# LCDTFT_CTRL_FT811.net
KiCad netlist of a schematic drawn in Altium Designer
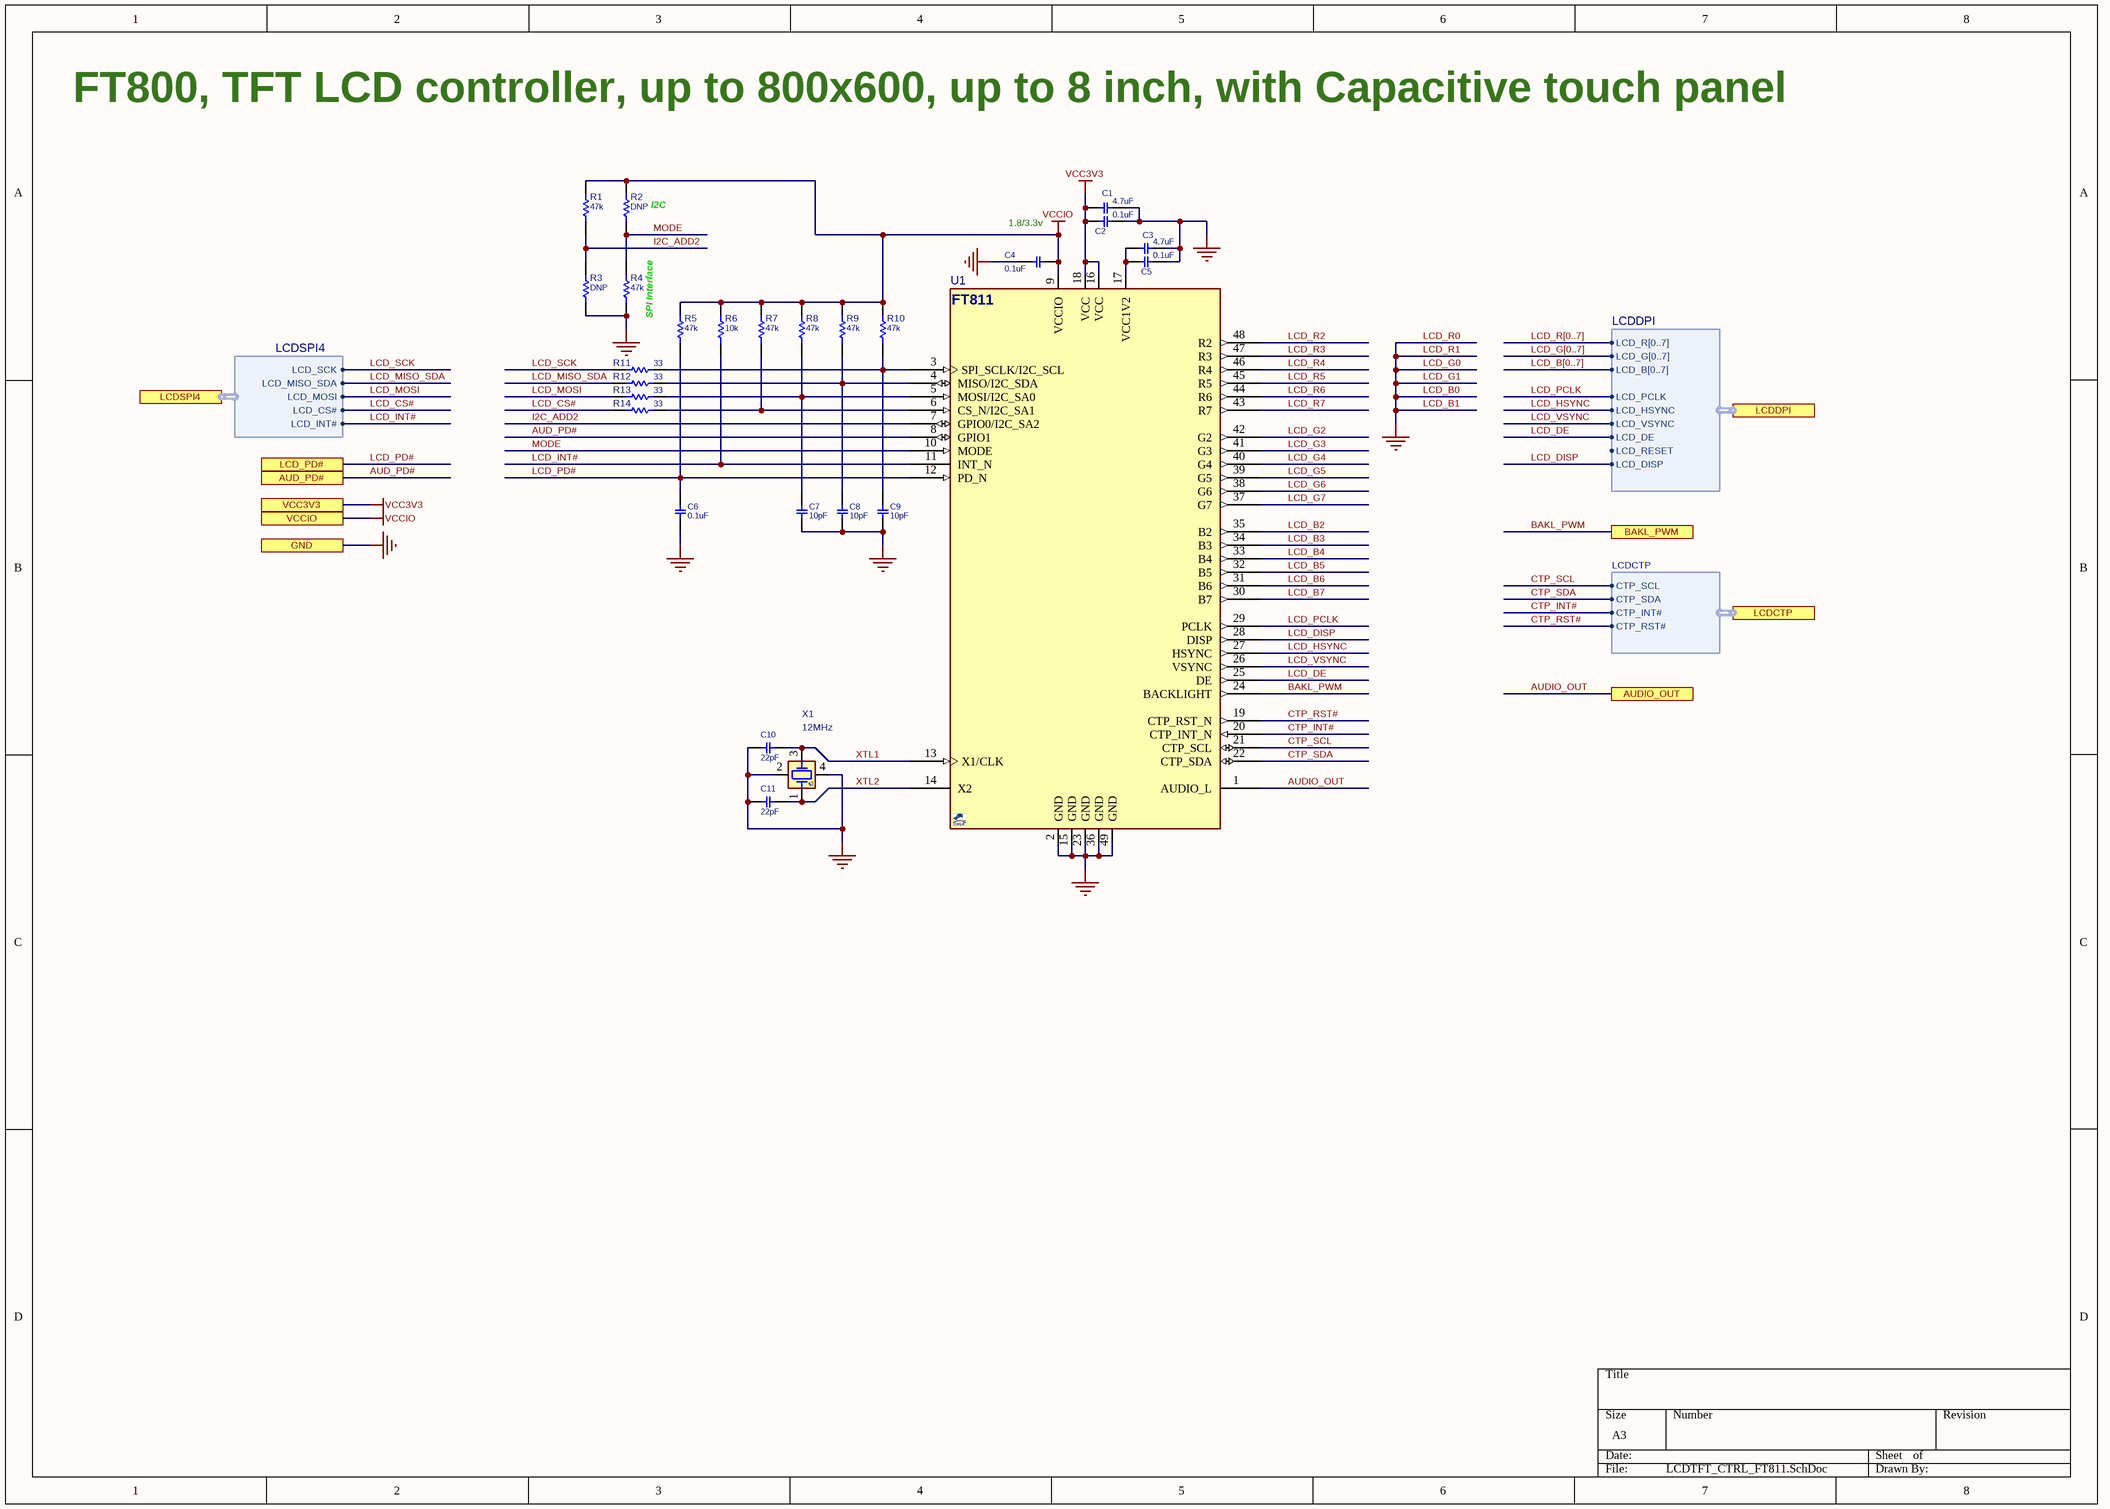
[diagram p0: LCDTFT_CTRL_FT811.SchDoc]

(export (version "E")
  (design (tool "Eeschema 10.0.6"))
  (components
    (comp (ref "C1")
      (value "4.7uF")
      (footprint "C0603")
      (description "CAP, MLCC")
      (libsource (lib "passive_smd") (part "CAP_SMD_MLCC"))
    )
    (comp (ref "C2")
      (value "0.1uF")
      (footprint "C0402")
      (description "CAP, MLCC")
      (fields (field (name "MANF_P#") "GRM155R71H104KE14D") (field (name "MANF") "Murata"))
      (libsource (lib "passive_smd") (part "CAP_SMD_MLCC"))
    )
    (comp (ref "C3")
      (value "4.7uF")
      (footprint "C0603")
      (description "CAP, MLCC")
      (libsource (lib "passive_smd") (part "CAP_SMD_MLCC"))
    )
    (comp (ref "C4")
      (value "0.1uF")
      (footprint "C0402")
      (description "CAP, MLCC")
      (fields (field (name "MANF_P#") "GRM155R71H104KE14D") (field (name "MANF") "Murata"))
      (libsource (lib "passive_smd") (part "CAP_SMD_MLCC"))
    )
    (comp (ref "C5")
      (value "0.1uF")
      (footprint "C0402")
      (description "CAP, MLCC")
      (fields (field (name "MANF_P#") "GRM155R71H104KE14D") (field (name "MANF") "Murata"))
      (libsource (lib "passive_smd") (part "CAP_SMD_MLCC"))
    )
    (comp (ref "C6")
      (value "0.1uF")
      (footprint "C0402")
      (description "CAP, MLCC")
      (fields (field (name "MANF_P#") "GRM155R71H104KE14D") (field (name "MANF") "Murata"))
      (libsource (lib "passive_smd") (part "CAP_SMD_MLCC"))
    )
    (comp (ref "C7")
      (value "10pF")
      (footprint "C0402")
      (description "CAP, MLCC")
      (libsource (lib "passive_smd") (part "CAP_SMD_MLCC"))
    )
    (comp (ref "C8")
      (value "10pF")
      (footprint "C0402")
      (description "CAP, MLCC")
      (libsource (lib "passive_smd") (part "CAP_SMD_MLCC"))
    )
    (comp (ref "C9")
      (value "10pF")
      (footprint "C0402")
      (description "CAP, MLCC")
      (libsource (lib "passive_smd") (part "CAP_SMD_MLCC"))
    )
    (comp (ref "C10")
      (value "22pF")
      (footprint "C0402")
      (description "CAP, MLCC")
      (libsource (lib "passive_smd") (part "CAP_SMD_MLCC"))
    )
    (comp (ref "C11")
      (value "22pF")
      (footprint "C0402")
      (description "CAP, MLCC")
      (libsource (lib "passive_smd") (part "CAP_SMD_MLCC"))
    )
    (comp (ref "R1")
      (value "47k")
      (footprint "R0402")
      (description "RESISTOR, SMD")
      (libsource (lib "passive_res_smd") (part "RES_SMD"))
    )
    (comp (ref "R2")
      (value "DNP")
      (footprint "R0402")
      (description "RESISTOR, SMD")
      (libsource (lib "passive_res_smd") (part "RES_SMD"))
    )
    (comp (ref "R3")
      (value "DNP")
      (footprint "R0402")
      (description "RESISTOR, SMD")
      (libsource (lib "passive_res_smd") (part "RES_SMD"))
    )
    (comp (ref "R4")
      (value "47k")
      (footprint "R0402")
      (description "RESISTOR, SMD")
      (libsource (lib "passive_res_smd") (part "RES_SMD"))
    )
    (comp (ref "R5")
      (value "47k")
      (footprint "R0402")
      (description "RESISTOR, SMD")
      (libsource (lib "passive_res_smd") (part "RES_SMD"))
    )
    (comp (ref "R6")
      (value "10k")
      (footprint "R0402")
      (description "RESISTOR, SMD")
      (libsource (lib "passive_res_smd") (part "RES_SMD"))
    )
    (comp (ref "R7")
      (value "47k")
      (footprint "R0402")
      (description "RESISTOR, SMD")
      (libsource (lib "passive_res_smd") (part "RES_SMD"))
    )
    (comp (ref "R8")
      (value "47k")
      (footprint "R0402")
      (description "RESISTOR, SMD")
      (libsource (lib "passive_res_smd") (part "RES_SMD"))
    )
    (comp (ref "R9")
      (value "47k")
      (footprint "R0402")
      (description "RESISTOR, SMD")
      (libsource (lib "passive_res_smd") (part "RES_SMD"))
    )
    (comp (ref "R10")
      (value "47k")
      (footprint "R0402")
      (description "RESISTOR, SMD")
      (libsource (lib "passive_res_smd") (part "RES_SMD"))
    )
    (comp (ref "R11")
      (value "33")
      (footprint "R0402")
      (description "RESISTOR, SMD")
      (libsource (lib "passive_res_smd") (part "RES_SMD"))
    )
    (comp (ref "R12")
      (value "33")
      (footprint "R0402")
      (description "RESISTOR, SMD")
      (libsource (lib "passive_res_smd") (part "RES_SMD"))
    )
    (comp (ref "R13")
      (value "33")
      (footprint "R0402")
      (description "RESISTOR, SMD")
      (libsource (lib "passive_res_smd") (part "RES_SMD"))
    )
    (comp (ref "R14")
      (value "33")
      (footprint "R0402")
      (description "RESISTOR, SMD")
      (libsource (lib "passive_res_smd") (part "RES_SMD"))
    )
    (comp (ref "U1")
      (value "FT811")
      (footprint "QFN50_48T")
      (description "LCD Display Controller, Embedded Video Engine, QFN-48")
      (fields (field (name "MANF") "FTDI/Bridgetek") (field (name "MANF_P#") "FT811Q"))
      (libsource (lib "lcdtft_controller") (part "FT811_QFN48"))
    )
    (comp (ref "X1")
      (value "12MHz")
      (footprint "XTL_4_3225")
      (description "Crystal 12MHz")
      (fields (field (name "MANF") "ECS") (field (name "MANF_P#") "ECS-120-18-33-JEM-TR"))
      (libsource (lib "crystal") (part "XTL_4_12MHz_3225"))
    )
  )
  (nets
    (net (code "4") (name "/AUDIO_OUT") (class "Default")
      (node (ref "U1") (pin "1") (pinfunction "AUDIO_L_1") (pintype "tri_state"))
    )
    (net (code "5") (name "/AUD_PD#") (class "Default")
      (node (ref "U1") (pin "8") (pinfunction "GPIO1_8") (pintype "bidirectional"))
    )
    (net (code "6") (name "/BAKL_PWM") (class "Default")
      (node (ref "U1") (pin "24") (pinfunction "BACKLIGHT_24") (pintype "output"))
    )
    (net (code "7") (name "/CTP_INT#") (class "Default")
      (node (ref "U1") (pin "20") (pinfunction "CTP_INT_N_20") (pintype "input"))
    )
    (net (code "8") (name "/CTP_RST#") (class "Default")
      (node (ref "U1") (pin "19") (pinfunction "CTP_RST_N_19") (pintype "output"))
    )
    (net (code "9") (name "/CTP_SCL") (class "Default")
      (node (ref "U1") (pin "21") (pinfunction "CTP_SCL_21") (pintype "bidirectional"))
    )
    (net (code "10") (name "/CTP_SDA") (class "Default")
      (node (ref "U1") (pin "22") (pinfunction "CTP_SDA_22") (pintype "bidirectional"))
    )
    (net (code "11") (name "/I2C_ADD2") (class "Default")
      (node (ref "R1") (pin "2") (pinfunction "2_2") (pintype "passive"))
      (node (ref "R3") (pin "1") (pinfunction "1_1") (pintype "passive"))
      (node (ref "U1") (pin "7") (pinfunction "GPIO0/I2C_SA2_7") (pintype "bidirectional"))
    )
    (net (code "12") (name "/LCD_B2") (class "Default")
      (node (ref "U1") (pin "35") (pinfunction "B2_35") (pintype "output"))
    )
    (net (code "13") (name "/LCD_B3") (class "Default")
      (node (ref "U1") (pin "34") (pinfunction "B3_34") (pintype "output"))
    )
    (net (code "14") (name "/LCD_B4") (class "Default")
      (node (ref "U1") (pin "33") (pinfunction "B4_33") (pintype "output"))
    )
    (net (code "15") (name "/LCD_B5") (class "Default")
      (node (ref "U1") (pin "32") (pinfunction "B5_32") (pintype "output"))
    )
    (net (code "16") (name "/LCD_B6") (class "Default")
      (node (ref "U1") (pin "31") (pinfunction "B6_31") (pintype "output"))
    )
    (net (code "17") (name "/LCD_B7") (class "Default")
      (node (ref "U1") (pin "30") (pinfunction "B7_30") (pintype "output"))
    )
    (net (code "19") (name "/LCD_CS#") (class "Default")
      (node (ref "R14") (pin "1") (pinfunction "1_1") (pintype "passive"))
    )
    (net (code "20") (name "/LCD_DE") (class "Default")
      (node (ref "U1") (pin "25") (pinfunction "DE_25") (pintype "output"))
    )
    (net (code "21") (name "/LCD_DISP") (class "Default")
      (node (ref "U1") (pin "28") (pinfunction "DISP_28") (pintype "output"))
    )
    (net (code "22") (name "/LCD_G2") (class "Default")
      (node (ref "U1") (pin "42") (pinfunction "G2_42") (pintype "output"))
    )
    (net (code "23") (name "/LCD_G3") (class "Default")
      (node (ref "U1") (pin "41") (pinfunction "G3_41") (pintype "output"))
    )
    (net (code "24") (name "/LCD_G4") (class "Default")
      (node (ref "U1") (pin "40") (pinfunction "G4_40") (pintype "output"))
    )
    (net (code "25") (name "/LCD_G5") (class "Default")
      (node (ref "U1") (pin "39") (pinfunction "G5_39") (pintype "output"))
    )
    (net (code "26") (name "/LCD_G6") (class "Default")
      (node (ref "U1") (pin "38") (pinfunction "G6_38") (pintype "output"))
    )
    (net (code "27") (name "/LCD_G7") (class "Default")
      (node (ref "U1") (pin "37") (pinfunction "G7_37") (pintype "output"))
    )
    (net (code "29") (name "/LCD_HSYNC") (class "Default")
      (node (ref "U1") (pin "27") (pinfunction "HSYNC_27") (pintype "output"))
    )
    (net (code "30") (name "/LCD_INT#") (class "Default")
      (node (ref "R6") (pin "2") (pinfunction "2_2") (pintype "passive"))
      (node (ref "U1") (pin "11") (pinfunction "INT_N_11") (pintype "tri_state"))
    )
    (net (code "31") (name "/LCD_MISO_SDA") (class "Default")
      (node (ref "R12") (pin "1") (pinfunction "1_1") (pintype "passive"))
    )
    (net (code "32") (name "/LCD_MOSI") (class "Default")
      (node (ref "R13") (pin "1") (pinfunction "1_1") (pintype "passive"))
    )
    (net (code "33") (name "/LCD_PCLK") (class "Default")
      (node (ref "U1") (pin "29") (pinfunction "PCLK_29") (pintype "output"))
    )
    (net (code "34") (name "/LCD_PD#") (class "Default")
      (node (ref "C6") (pin "1") (pinfunction "1_1") (pintype "passive"))
      (node (ref "R5") (pin "2") (pinfunction "2_2") (pintype "passive"))
      (node (ref "U1") (pin "12") (pinfunction "PD_N_12") (pintype "input"))
    )
    (net (code "35") (name "/LCD_R2") (class "Default")
      (node (ref "U1") (pin "48") (pinfunction "R2_48") (pintype "output"))
    )
    (net (code "36") (name "/LCD_R3") (class "Default")
      (node (ref "U1") (pin "47") (pinfunction "R3_47") (pintype "output"))
    )
    (net (code "37") (name "/LCD_R4") (class "Default")
      (node (ref "U1") (pin "46") (pinfunction "R4_46") (pintype "output"))
    )
    (net (code "38") (name "/LCD_R5") (class "Default")
      (node (ref "U1") (pin "45") (pinfunction "R5_45") (pintype "output"))
    )
    (net (code "39") (name "/LCD_R6") (class "Default")
      (node (ref "U1") (pin "44") (pinfunction "R6_44") (pintype "output"))
    )
    (net (code "40") (name "/LCD_R7") (class "Default")
      (node (ref "U1") (pin "43") (pinfunction "R7_43") (pintype "output"))
    )
    (net (code "42") (name "/LCD_SCK") (class "Default")
      (node (ref "R11") (pin "1") (pinfunction "1_1") (pintype "passive"))
    )
    (net (code "43") (name "/LCD_VSYNC") (class "Default")
      (node (ref "U1") (pin "26") (pinfunction "VSYNC_26") (pintype "output"))
    )
    (net (code "44") (name "/MODE") (class "Default")
      (node (ref "R2") (pin "2") (pinfunction "2_2") (pintype "passive"))
      (node (ref "R4") (pin "1") (pinfunction "1_1") (pintype "passive"))
      (node (ref "U1") (pin "10") (pinfunction "MODE_10") (pintype "input"))
    )
    (net (code "45") (name "/XTL1") (class "Default")
      (node (ref "C10") (pin "2") (pinfunction "2_2") (pintype "passive"))
      (node (ref "U1") (pin "13") (pinfunction "X1/CLK_13") (pintype "input"))
      (node (ref "X1") (pin "3") (pinfunction "2_3") (pintype "passive"))
    )
    (net (code "46") (name "/XTL2") (class "Default")
      (node (ref "C11") (pin "1") (pinfunction "1_1") (pintype "passive"))
      (node (ref "U1") (pin "14") (pinfunction "X2_14") (pintype "passive"))
      (node (ref "X1") (pin "1") (pinfunction "1_1") (pintype "passive"))
    )
    (net (code "50") (name "GND") (class "Default")
      (node (ref "C1") (pin "1") (pinfunction "1_1") (pintype "passive"))
      (node (ref "C10") (pin "1") (pinfunction "1_1") (pintype "passive"))
      (node (ref "C11") (pin "2") (pinfunction "2_2") (pintype "passive"))
      (node (ref "C2") (pin "1") (pinfunction "1_1") (pintype "passive"))
      (node (ref "C3") (pin "1") (pinfunction "1_1") (pintype "passive"))
      (node (ref "C4") (pin "2") (pinfunction "2_2") (pintype "passive"))
      (node (ref "C5") (pin "1") (pinfunction "1_1") (pintype "passive"))
      (node (ref "C6") (pin "2") (pinfunction "2_2") (pintype "passive"))
      (node (ref "C7") (pin "2") (pinfunction "2_2") (pintype "passive"))
      (node (ref "C8") (pin "2") (pinfunction "2_2") (pintype "passive"))
      (node (ref "C9") (pin "2") (pinfunction "2_2") (pintype "passive"))
      (node (ref "R3") (pin "2") (pinfunction "2_2") (pintype "passive"))
      (node (ref "R4") (pin "2") (pinfunction "2_2") (pintype "passive"))
      (node (ref "U1") (pin "15") (pinfunction "GND_15") (pintype "power_in"))
      (node (ref "U1") (pin "2") (pinfunction "GND_2") (pintype "power_in"))
      (node (ref "U1") (pin "23") (pinfunction "GND_23") (pintype "power_in"))
      (node (ref "U1") (pin "36") (pinfunction "GND_36") (pintype "power_in"))
      (node (ref "U1") (pin "49") (pinfunction "GND_49") (pintype "power_in"))
      (node (ref "X1") (pin "2") (pinfunction "2_2") (pintype "passive"))
      (node (ref "X1") (pin "4") (pinfunction "4_4") (pintype "passive"))
    )
    (net (code "51") (name "Net-(U1-CS_N{slash}I2C_SA1)") (class "Default")
      (node (ref "R14") (pin "2") (pinfunction "2_2") (pintype "passive"))
      (node (ref "R7") (pin "2") (pinfunction "2_2") (pintype "passive"))
      (node (ref "U1") (pin "6") (pinfunction "CS_N/I2C_SA1_6") (pintype "input"))
    )
    (net (code "52") (name "Net-(U1-MISO{slash}I2C_SDA)") (class "Default")
      (node (ref "C8") (pin "1") (pinfunction "1_1") (pintype "passive"))
      (node (ref "R12") (pin "2") (pinfunction "2_2") (pintype "passive"))
      (node (ref "R9") (pin "2") (pinfunction "2_2") (pintype "passive"))
      (node (ref "U1") (pin "4") (pinfunction "MISO/I2C_SDA_4") (pintype "bidirectional"))
    )
    (net (code "53") (name "Net-(U1-MOSI{slash}I2C_SA0)") (class "Default")
      (node (ref "C7") (pin "1") (pinfunction "1_1") (pintype "passive"))
      (node (ref "R13") (pin "2") (pinfunction "2_2") (pintype "passive"))
      (node (ref "R8") (pin "2") (pinfunction "2_2") (pintype "passive"))
      (node (ref "U1") (pin "5") (pinfunction "MOSI/I2C_SA0_5") (pintype "input"))
    )
    (net (code "54") (name "Net-(U1-SPI_SCLK{slash}I2C_SCL)") (class "Default")
      (node (ref "C9") (pin "1") (pinfunction "1_1") (pintype "passive"))
      (node (ref "R10") (pin "2") (pinfunction "2_2") (pintype "passive"))
      (node (ref "R11") (pin "2") (pinfunction "2_2") (pintype "passive"))
      (node (ref "U1") (pin "3") (pinfunction "SPI_SCLK/I2C_SCL_3") (pintype "input"))
    )
    (net (code "55") (name "Net-(U1-VCC1V2)") (class "Default")
      (node (ref "C3") (pin "2") (pinfunction "2_2") (pintype "passive"))
      (node (ref "C5") (pin "2") (pinfunction "2_2") (pintype "passive"))
      (node (ref "U1") (pin "17") (pinfunction "VCC1V2_17") (pintype "power_in"))
    )
    (net (code "56") (name "VCC3V3") (class "Default")
      (node (ref "C1") (pin "2") (pinfunction "2_2") (pintype "passive"))
      (node (ref "C2") (pin "2") (pinfunction "2_2") (pintype "passive"))
      (node (ref "U1") (pin "16") (pinfunction "VCC_16") (pintype "power_in"))
      (node (ref "U1") (pin "18") (pinfunction "VCC_18") (pintype "power_in"))
    )
    (net (code "57") (name "VCCIO") (class "Default")
      (node (ref "C4") (pin "1") (pinfunction "1_1") (pintype "passive"))
      (node (ref "R1") (pin "1") (pinfunction "1_1") (pintype "passive"))
      (node (ref "R10") (pin "1") (pinfunction "1_1") (pintype "passive"))
      (node (ref "R2") (pin "1") (pinfunction "1_1") (pintype "passive"))
      (node (ref "R5") (pin "1") (pinfunction "1_1") (pintype "passive"))
      (node (ref "R6") (pin "1") (pinfunction "1_1") (pintype "passive"))
      (node (ref "R7") (pin "1") (pinfunction "1_1") (pintype "passive"))
      (node (ref "R8") (pin "1") (pinfunction "1_1") (pintype "passive"))
      (node (ref "R9") (pin "1") (pinfunction "1_1") (pintype "passive"))
      (node (ref "U1") (pin "9") (pinfunction "VCCIO_9") (pintype "power_in"))
    )
  )
)
